# MCU.net
KiCad netlist of a schematic drawn in Altium Designer
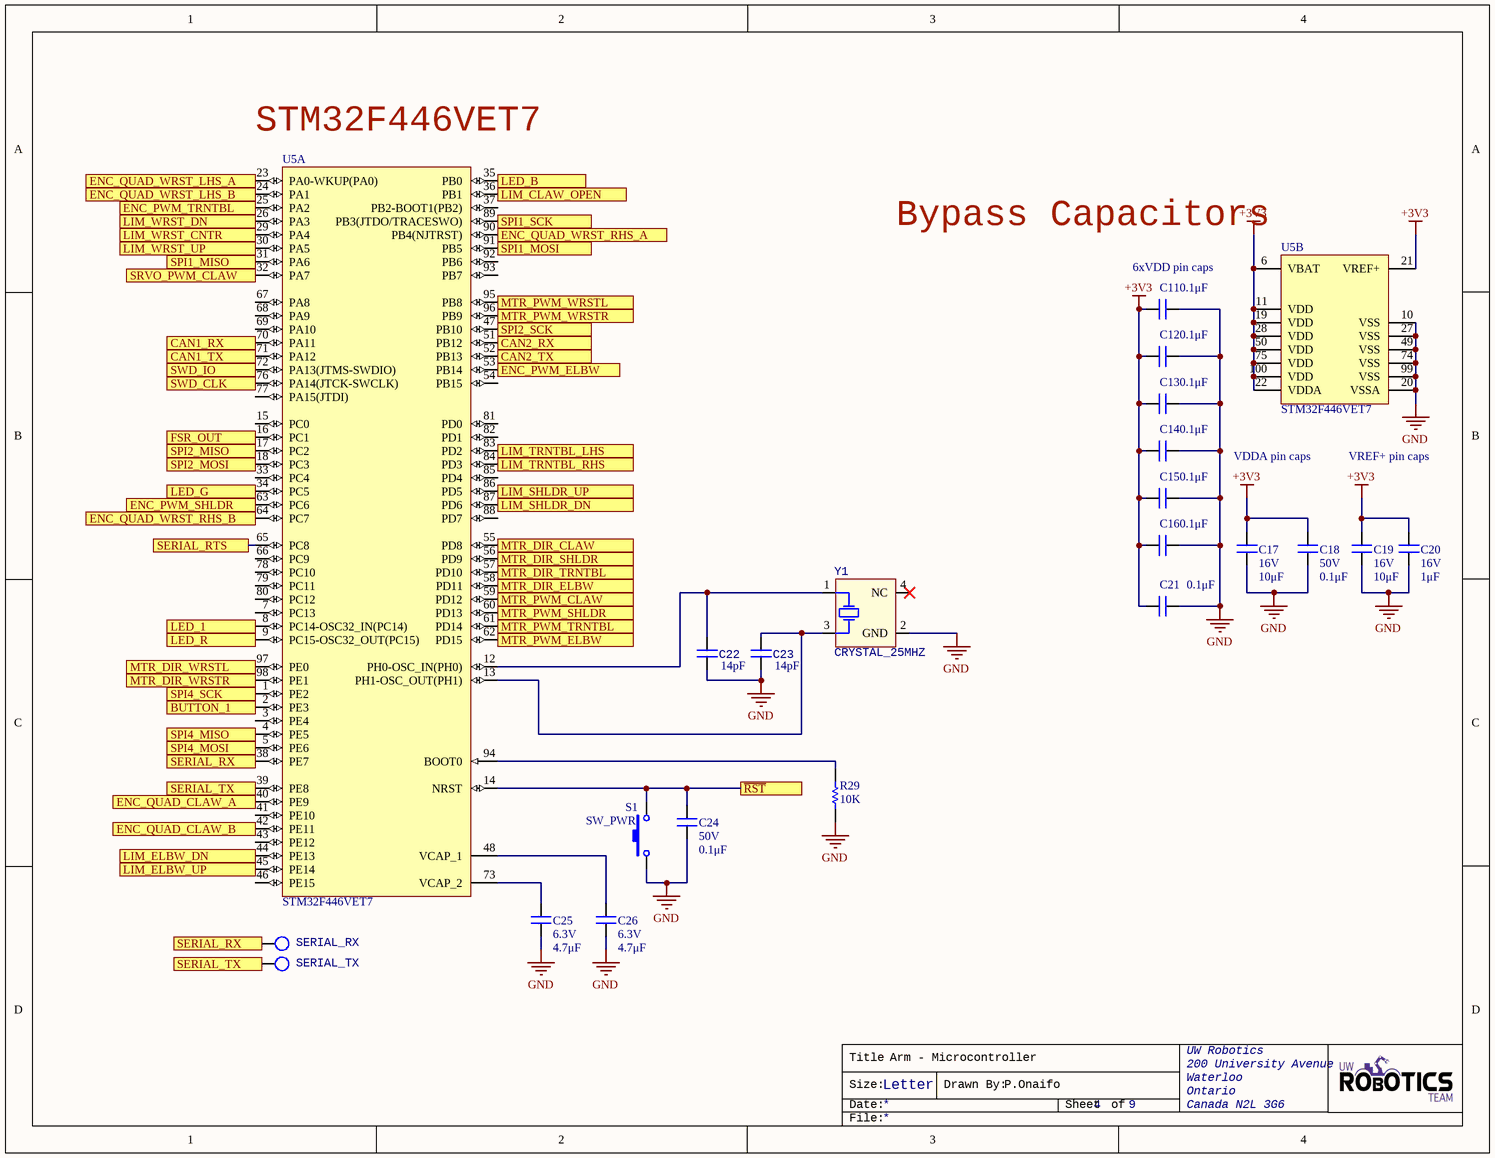
[diagram p0: MCU.SchDoc]

(export (version "E")
  (design (tool "Eeschema 10.0.6"))
  (components
    (comp (ref "C11")
      (value "0.1μF")
      (footprint "CAPC0603(1608)55_N")
      (description "CAP CER 0.1UF 50V X7R 0603")
      (fields (field (name "Comment") "CAP_0.1uF_50V_0603"))
      (libsource (lib "UWRT_Schematic_Library_2020") (part "CAP_0.1uF_50V_0603"))
    )
    (comp (ref "C12")
      (value "0.1μF")
      (footprint "CAPC0603(1608)55_N")
      (description "CAP CER 0.1UF 50V X7R 0603")
      (fields (field (name "Comment") "CAP_0.1uF_50V_0603"))
      (libsource (lib "UWRT_Schematic_Library_2020") (part "CAP_0.1uF_50V_0603"))
    )
    (comp (ref "C13")
      (value "0.1μF")
      (footprint "CAPC0603(1608)55_N")
      (description "CAP CER 0.1UF 50V X7R 0603")
      (fields (field (name "Comment") "CAP_0.1uF_50V_0603"))
      (libsource (lib "UWRT_Schematic_Library_2020") (part "CAP_0.1uF_50V_0603"))
    )
    (comp (ref "C14")
      (value "0.1μF")
      (footprint "CAPC0603(1608)55_N")
      (description "CAP CER 0.1UF 50V X7R 0603")
      (fields (field (name "Comment") "CAP_0.1uF_50V_0603"))
      (libsource (lib "UWRT_Schematic_Library_2020") (part "CAP_0.1uF_50V_0603"))
    )
    (comp (ref "C15")
      (value "0.1μF")
      (footprint "CAPC0603(1608)55_N")
      (description "CAP CER 0.1UF 50V X7R 0603")
      (fields (field (name "Comment") "CAP_0.1uF_50V_0603"))
      (libsource (lib "UWRT_Schematic_Library_2020") (part "CAP_0.1uF_50V_0603"))
    )
    (comp (ref "C16")
      (value "0.1μF")
      (footprint "CAPC0603(1608)55_N")
      (description "CAP CER 0.1UF 50V X7R 0603")
      (fields (field (name "Comment") "CAP_0.1uF_50V_0603"))
      (libsource (lib "UWRT_Schematic_Library_2020") (part "CAP_0.1uF_50V_0603"))
    )
    (comp (ref "C17")
      (value "10μF")
      (footprint "CAPC0603(1608)55_N")
      (description "CAP CER 10000PF 16V X7R 0603")
      (fields (field (name "VOLTAGE RATING") "16V") (field (name "Comment") "CAP_10nF_0603"))
      (libsource (lib "UWRT_Schematic_Library_2020") (part "CAP_10nF_0603"))
    )
    (comp (ref "C18")
      (value "0.1μF")
      (footprint "CAPC0603(1608)55_N")
      (description "CAP CER 0.1UF 50V X7R 0603")
      (fields (field (name "VOLTAGE RATING") "50V") (field (name "Comment") "CAP_0.1uF_50V_0603"))
      (libsource (lib "UWRT_Schematic_Library_2020") (part "CAP_0.1uF_50V_0603"))
    )
    (comp (ref "C19")
      (value "10μF")
      (footprint "CAPC0603(1608)55_N")
      (description "CAP CER 10000PF 16V X7R 0603")
      (fields (field (name "VOLTAGE RATING") "16V") (field (name "Comment") "CAP_10nF_0603"))
      (libsource (lib "UWRT_Schematic_Library_2020") (part "CAP_10nF_0603"))
    )
    (comp (ref "C20")
      (value "1μF")
      (footprint "CAPC0603(1608)55_N")
      (description "CAP CER 1UF 16V Y5V 0603")
      (fields
        (field (name "VOLTAGE RATING") "16V")
        (field (name "MANUFACTURER PART NUMBER") "CC0603ZRY5V7BB105")
        (field (name "Comment") "CAP_1uF_16V_0603")
      )
      (libsource (lib "UWRT_Schematic_Library_2020") (part "CAP_1uF_16V_0603"))
    )
    (comp (ref "C21")
      (value "0.1μF")
      (footprint "CAPC0603(1608)55_N")
      (description "CAP CER 0.1UF 50V X7R 0603")
      (fields (field (name "Comment") "CAP_0.1uF_50V_0603"))
      (libsource (lib "UWRT_Schematic_Library_2020") (part "CAP_0.1uF_50V_0603"))
    )
    (comp (ref "C22")
      (value "14pF")
      (description "CAP CER 14PF 50V C0G/NP0 0603")
      (fields (field (name "TOLERANCE") "5%") (field (name "Comment") "CAP_14pF_50V_0603"))
      (libsource (lib "UWRT_Schematic_Library_2020") (part "CAP_14pF_50V_0603"))
    )
    (comp (ref "C23")
      (value "14pF")
      (description "CAP CER 14PF 50V C0G/NP0 0603")
      (fields (field (name "TOLERANCE") "5%") (field (name "Comment") "CAP_14pF_50V_0603"))
      (libsource (lib "UWRT_Schematic_Library_2020") (part "CAP_14pF_50V_0603"))
    )
    (comp (ref "C24")
      (value "0.1μF")
      (footprint "CAPC0603(1608)55_N")
      (description "CAP CER 0.1UF 50V X7R 0603")
      (fields (field (name "VOLTAGE RATING") "50V") (field (name "Comment") "CAP_0.1uF_50V_0603"))
      (libsource (lib "UWRT_Schematic_Library_2020") (part "CAP_0.1uF_50V_0603"))
    )
    (comp (ref "C25")
      (value "4.7μF")
      (footprint "CAPC0603(1608)55_N")
      (description "CAP CER 4.7UF 6.3V X5R 0603")
      (fields (field (name "VOLTAGE RATING") "6.3V") (field (name "Comment") "CAP_4.7uF_0603"))
      (libsource (lib "UWRT_Schematic_Library_2020") (part "CAP_4.7uF_0603"))
    )
    (comp (ref "C26")
      (value "4.7μF")
      (footprint "CAPC0603(1608)55_N")
      (description "CAP CER 4.7UF 6.3V X5R 0603")
      (fields (field (name "VOLTAGE RATING") "6.3V") (field (name "Comment") "CAP_4.7uF_0603"))
      (libsource (lib "UWRT_Schematic_Library_2020") (part "CAP_4.7uF_0603"))
    )
    (comp (ref "R29")
      (value "10K")
      (footprint "RESC0603(1608)_N")
      (description "RES SMD 10K OHM 5% 1/10W 0603")
      (fields (field (name "MANUFACTURER") "Yageo") (field (name "MPN") "RC0603JR-0710KL"))
      (libsource (lib "UWRT_Schematic_Library_2020") (part "RES_10K_0603"))
    )
    (comp (ref "S1")
      (value "SW_PWR")
      (footprint "PTS830GM140")
      (description "Power Switch (Red)")
      (libsource (lib "UWRT_Schematic_Library_2020") (part "SW_PWR"))
    )
    (comp (ref "SERIAL_RX")
      (value "TESTPOINT_LOOP")
      (footprint "TESTPOINT_LOOP")
      (description "Loop testpoint through-hole pad")
      (libsource (lib "UWRT_Schematic_Library_2020") (part "TESTPOINT_LOOP"))
    )
    (comp (ref "SERIAL_TX")
      (value "TESTPOINT_LOOP")
      (footprint "TESTPOINT_LOOP")
      (description "Loop testpoint through-hole pad")
      (libsource (lib "UWRT_Schematic_Library_2020") (part "TESTPOINT_LOOP"))
    )
    (comp (ref "U5")
      (value "STM32F446VET7")
      (footprint "STM-LQFP100_L")
      (libsource (lib "Altium Content Vault") (part "MC-ARM-STM32F446-LQFP100"))
    )
    (comp (ref "Y1")
      (value "CRYSTAL_25MHZ")
      (footprint "SOIC254P1016X440-4N")
      (description "CRYSTAL 25.0000MHZ 12PF SMD")
      (libsource (lib "UWRT_Schematic_Library_2020") (part "CRYSTAL_25MHZ"))
    )
  )
  (nets
    (net (code "1") (name "+3V3") (class "Default")
      (node (ref "C11") (pin "1") (pinfunction "1_1") (pintype "passive"))
      (node (ref "C12") (pin "1") (pinfunction "1_1") (pintype "passive"))
      (node (ref "C13") (pin "1") (pinfunction "1_1") (pintype "passive"))
      (node (ref "C14") (pin "1") (pinfunction "1_1") (pintype "passive"))
      (node (ref "C15") (pin "1") (pinfunction "1_1") (pintype "passive"))
      (node (ref "C16") (pin "1") (pinfunction "1_1") (pintype "passive"))
      (node (ref "C17") (pin "2") (pinfunction "2_2") (pintype "passive"))
      (node (ref "C18") (pin "2") (pinfunction "2_2") (pintype "passive"))
      (node (ref "C19") (pin "1") (pinfunction "1_1") (pintype "passive"))
      (node (ref "C20") (pin "2") (pinfunction "2_2") (pintype "passive"))
      (node (ref "C21") (pin "1") (pinfunction "1_1") (pintype "passive"))
      (node (ref "U5") (pin "100") (pinfunction "VDD_100") (pintype "power_in"))
      (node (ref "U5") (pin "11") (pinfunction "VDD_11") (pintype "power_in"))
      (node (ref "U5") (pin "19") (pinfunction "VDD_19") (pintype "power_in"))
      (node (ref "U5") (pin "21") (pinfunction "VREF+_21") (pintype "power_in"))
      (node (ref "U5") (pin "22") (pinfunction "VDDA_22") (pintype "power_in"))
      (node (ref "U5") (pin "28") (pinfunction "VDD_28") (pintype "power_in"))
      (node (ref "U5") (pin "50") (pinfunction "VDD_50") (pintype "power_in"))
      (node (ref "U5") (pin "6") (pinfunction "VBAT_6") (pintype "power_in"))
      (node (ref "U5") (pin "75") (pinfunction "VDD_75") (pintype "power_in"))
    )
    (net (code "2") (name "/BUTTON_1") (class "Default")
      (node (ref "U5") (pin "2") (pinfunction "PE3_2") (pintype "bidirectional"))
    )
    (net (code "3") (name "/CAN1_RX") (class "Default")
      (node (ref "U5") (pin "70") (pinfunction "PA11_70") (pintype "bidirectional"))
    )
    (net (code "4") (name "/CAN1_TX") (class "Default")
      (node (ref "U5") (pin "71") (pinfunction "PA12_71") (pintype "bidirectional"))
    )
    (net (code "5") (name "/CAN2_RX") (class "Default")
      (node (ref "U5") (pin "51") (pinfunction "PB12_51") (pintype "bidirectional"))
    )
    (net (code "6") (name "/CAN2_TX") (class "Default")
      (node (ref "U5") (pin "52") (pinfunction "PB13_52") (pintype "bidirectional"))
    )
    (net (code "7") (name "/ENC_PWM_ELBW") (class "Default")
      (node (ref "U5") (pin "53") (pinfunction "PB14_53") (pintype "bidirectional"))
    )
    (net (code "8") (name "/ENC_PWM_SHLDR") (class "Default")
      (node (ref "U5") (pin "63") (pinfunction "PC6_63") (pintype "bidirectional"))
    )
    (net (code "9") (name "/ENC_PWM_TRNTBL") (class "Default")
      (node (ref "U5") (pin "25") (pinfunction "PA2_25") (pintype "bidirectional"))
    )
    (net (code "10") (name "/ENC_QUAD_CLAW_A") (class "Default")
      (node (ref "U5") (pin "40") (pinfunction "PE9_40") (pintype "bidirectional"))
    )
    (net (code "11") (name "/ENC_QUAD_CLAW_B") (class "Default")
      (node (ref "U5") (pin "42") (pinfunction "PE11_42") (pintype "bidirectional"))
    )
    (net (code "12") (name "/ENC_QUAD_WRST_LHS_A") (class "Default")
      (node (ref "U5") (pin "23") (pinfunction "PA0-WKUP(PA0)_23") (pintype "bidirectional"))
    )
    (net (code "13") (name "/ENC_QUAD_WRST_LHS_B") (class "Default")
      (node (ref "U5") (pin "24") (pinfunction "PA1_24") (pintype "bidirectional"))
    )
    (net (code "14") (name "/ENC_QUAD_WRST_RHS_A") (class "Default")
      (node (ref "U5") (pin "90") (pinfunction "PB4(NJTRST)_90") (pintype "bidirectional"))
    )
    (net (code "15") (name "/ENC_QUAD_WRST_RHS_B") (class "Default")
      (node (ref "U5") (pin "64") (pinfunction "PC7_64") (pintype "bidirectional"))
    )
    (net (code "16") (name "/FSR_OUT") (class "Default")
      (node (ref "U5") (pin "16") (pinfunction "PC1_16") (pintype "bidirectional"))
    )
    (net (code "17") (name "/LED_1") (class "Default")
      (node (ref "U5") (pin "8") (pinfunction "PC14-OSC32_IN(PC14)_8") (pintype "bidirectional"))
    )
    (net (code "18") (name "/LED_B") (class "Default")
      (node (ref "U5") (pin "35") (pinfunction "PB0_35") (pintype "bidirectional"))
    )
    (net (code "19") (name "/LED_G") (class "Default")
      (node (ref "U5") (pin "34") (pinfunction "PC5_34") (pintype "bidirectional"))
    )
    (net (code "20") (name "/LED_R") (class "Default")
      (node (ref "U5") (pin "9") (pinfunction "PC15-OSC32_OUT(PC15)_9") (pintype "bidirectional"))
    )
    (net (code "21") (name "/LIM_CLAW_OPEN") (class "Default")
      (node (ref "U5") (pin "36") (pinfunction "PB1_36") (pintype "bidirectional"))
    )
    (net (code "22") (name "/LIM_ELBW_DN") (class "Default")
      (node (ref "U5") (pin "44") (pinfunction "PE13_44") (pintype "bidirectional"))
    )
    (net (code "23") (name "/LIM_ELBW_UP") (class "Default")
      (node (ref "U5") (pin "45") (pinfunction "PE14_45") (pintype "bidirectional"))
    )
    (net (code "24") (name "/LIM_SHLDR_DN") (class "Default")
      (node (ref "U5") (pin "87") (pinfunction "PD6_87") (pintype "bidirectional"))
    )
    (net (code "25") (name "/LIM_SHLDR_UP") (class "Default")
      (node (ref "U5") (pin "86") (pinfunction "PD5_86") (pintype "bidirectional"))
    )
    (net (code "26") (name "/LIM_TRNTBL_LHS") (class "Default")
      (node (ref "U5") (pin "83") (pinfunction "PD2_83") (pintype "bidirectional"))
    )
    (net (code "27") (name "/LIM_TRNTBL_RHS") (class "Default")
      (node (ref "U5") (pin "84") (pinfunction "PD3_84") (pintype "bidirectional"))
    )
    (net (code "28") (name "/LIM_WRST_CNTR") (class "Default")
      (node (ref "U5") (pin "29") (pinfunction "PA4_29") (pintype "bidirectional"))
    )
    (net (code "29") (name "/LIM_WRST_DN") (class "Default")
      (node (ref "U5") (pin "26") (pinfunction "PA3_26") (pintype "bidirectional"))
    )
    (net (code "30") (name "/LIM_WRST_UP") (class "Default")
      (node (ref "U5") (pin "30") (pinfunction "PA5_30") (pintype "bidirectional"))
    )
    (net (code "31") (name "/MTR_DIR_CLAW") (class "Default")
      (node (ref "U5") (pin "55") (pinfunction "PD8_55") (pintype "bidirectional"))
    )
    (net (code "32") (name "/MTR_DIR_ELBW") (class "Default")
      (node (ref "U5") (pin "58") (pinfunction "PD11_58") (pintype "bidirectional"))
    )
    (net (code "33") (name "/MTR_DIR_SHLDR") (class "Default")
      (node (ref "U5") (pin "56") (pinfunction "PD9_56") (pintype "bidirectional"))
    )
    (net (code "34") (name "/MTR_DIR_TRNTBL") (class "Default")
      (node (ref "U5") (pin "57") (pinfunction "PD10_57") (pintype "bidirectional"))
    )
    (net (code "35") (name "/MTR_DIR_WRSTL") (class "Default")
      (node (ref "U5") (pin "97") (pinfunction "PE0_97") (pintype "bidirectional"))
    )
    (net (code "36") (name "/MTR_DIR_WRSTR") (class "Default")
      (node (ref "U5") (pin "98") (pinfunction "PE1_98") (pintype "bidirectional"))
    )
    (net (code "37") (name "/MTR_PWM_CLAW") (class "Default")
      (node (ref "U5") (pin "59") (pinfunction "PD12_59") (pintype "bidirectional"))
    )
    (net (code "38") (name "/MTR_PWM_ELBW") (class "Default")
      (node (ref "U5") (pin "62") (pinfunction "PD15_62") (pintype "bidirectional"))
    )
    (net (code "39") (name "/MTR_PWM_SHLDR") (class "Default")
      (node (ref "U5") (pin "60") (pinfunction "PD13_60") (pintype "bidirectional"))
    )
    (net (code "40") (name "/MTR_PWM_TRNTBL") (class "Default")
      (node (ref "U5") (pin "61") (pinfunction "PD14_61") (pintype "bidirectional"))
    )
    (net (code "41") (name "/MTR_PWM_WRSTL") (class "Default")
      (node (ref "U5") (pin "95") (pinfunction "PB8_95") (pintype "bidirectional"))
    )
    (net (code "42") (name "/MTR_PWM_WRSTR") (class "Default")
      (node (ref "U5") (pin "96") (pinfunction "PB9_96") (pintype "bidirectional"))
    )
    (net (code "43") (name "/SERIAL_RTS") (class "Default")
      (node (ref "U5") (pin "65") (pinfunction "PC8_65") (pintype "bidirectional"))
    )
    (net (code "44") (name "/SERIAL_RX") (class "Default")
      (node (ref "SERIAL_RX") (pin "1") (pintype "passive"))
      (node (ref "U5") (pin "38") (pinfunction "PE7_38") (pintype "bidirectional"))
    )
    (net (code "45") (name "/SERIAL_TX") (class "Default")
      (node (ref "SERIAL_TX") (pin "1") (pintype "passive"))
      (node (ref "U5") (pin "39") (pinfunction "PE8_39") (pintype "bidirectional"))
    )
    (net (code "46") (name "/SPI1_MISO") (class "Default")
      (node (ref "U5") (pin "31") (pinfunction "PA6_31") (pintype "bidirectional"))
    )
    (net (code "47") (name "/SPI1_MOSI") (class "Default")
      (node (ref "U5") (pin "91") (pinfunction "PB5_91") (pintype "bidirectional"))
    )
    (net (code "48") (name "/SPI1_SCK") (class "Default")
      (node (ref "U5") (pin "89") (pinfunction "PB3(JTDO/TRACESWO)_89") (pintype "bidirectional"))
    )
    (net (code "49") (name "/SPI2_MISO") (class "Default")
      (node (ref "U5") (pin "17") (pinfunction "PC2_17") (pintype "bidirectional"))
    )
    (net (code "50") (name "/SPI2_MOSI") (class "Default")
      (node (ref "U5") (pin "18") (pinfunction "PC3_18") (pintype "bidirectional"))
    )
    (net (code "51") (name "/SPI2_SCK") (class "Default")
      (node (ref "U5") (pin "47") (pinfunction "PB10_47") (pintype "bidirectional"))
    )
    (net (code "52") (name "/SPI4_MISO") (class "Default")
      (node (ref "U5") (pin "4") (pinfunction "PE5_4") (pintype "bidirectional"))
    )
    (net (code "53") (name "/SPI4_MOSI") (class "Default")
      (node (ref "U5") (pin "5") (pinfunction "PE6_5") (pintype "bidirectional"))
    )
    (net (code "54") (name "/SPI4_SCK") (class "Default")
      (node (ref "U5") (pin "1") (pinfunction "PE2_1") (pintype "bidirectional"))
    )
    (net (code "55") (name "/SRVO_PWM_CLAW") (class "Default")
      (node (ref "U5") (pin "32") (pinfunction "PA7_32") (pintype "bidirectional"))
    )
    (net (code "56") (name "/SWD_CLK") (class "Default")
      (node (ref "U5") (pin "76") (pinfunction "PA14(JTCK-SWCLK)_76") (pintype "bidirectional"))
    )
    (net (code "57") (name "/SWD_IO") (class "Default")
      (node (ref "U5") (pin "72") (pinfunction "PA13(JTMS-SWDIO)_72") (pintype "bidirectional"))
    )
    (net (code "58") (name "/~{RST}") (class "Default")
      (node (ref "C24") (pin "2") (pinfunction "2_2") (pintype "passive"))
      (node (ref "S1") (pin "2") (pinfunction "2_2") (pintype "passive"))
      (node (ref "U5") (pin "14") (pinfunction "NRST_14") (pintype "bidirectional"))
    )
    (net (code "59") (name "GND") (class "Default")
      (node (ref "C11") (pin "2") (pinfunction "2_2") (pintype "passive"))
      (node (ref "C12") (pin "2") (pinfunction "2_2") (pintype "passive"))
      (node (ref "C13") (pin "2") (pinfunction "2_2") (pintype "passive"))
      (node (ref "C14") (pin "2") (pinfunction "2_2") (pintype "passive"))
      (node (ref "C15") (pin "2") (pinfunction "2_2") (pintype "passive"))
      (node (ref "C16") (pin "2") (pinfunction "2_2") (pintype "passive"))
      (node (ref "C17") (pin "1") (pinfunction "1_1") (pintype "passive"))
      (node (ref "C18") (pin "1") (pinfunction "1_1") (pintype "passive"))
      (node (ref "C19") (pin "2") (pinfunction "2_2") (pintype "passive"))
      (node (ref "C20") (pin "1") (pinfunction "1_1") (pintype "passive"))
      (node (ref "C21") (pin "2") (pinfunction "2_2") (pintype "passive"))
      (node (ref "C22") (pin "1") (pinfunction "1_1") (pintype "passive"))
      (node (ref "C23") (pin "1") (pinfunction "1_1") (pintype "passive"))
      (node (ref "C24") (pin "1") (pinfunction "1_1") (pintype "passive"))
      (node (ref "C25") (pin "1") (pinfunction "1_1") (pintype "passive"))
      (node (ref "C26") (pin "1") (pinfunction "1_1") (pintype "passive"))
      (node (ref "R29") (pin "2") (pinfunction "2_2") (pintype "passive"))
      (node (ref "S1") (pin "1") (pinfunction "1_1") (pintype "passive"))
      (node (ref "U5") (pin "10") (pinfunction "VSS_10") (pintype "power_in"))
      (node (ref "U5") (pin "20") (pinfunction "VSSA_20") (pintype "power_in"))
      (node (ref "U5") (pin "27") (pinfunction "VSS_27") (pintype "power_in"))
      (node (ref "U5") (pin "49") (pinfunction "VSS_49") (pintype "power_in"))
      (node (ref "U5") (pin "74") (pinfunction "VSS_74") (pintype "power_in"))
      (node (ref "U5") (pin "99") (pinfunction "VSS_99") (pintype "power_in"))
      (node (ref "Y1") (pin "2") (pinfunction "GND_2") (pintype "power_in"))
    )
    (net (code "60") (name "Net-(U5A-BOOT0)") (class "Default")
      (node (ref "R29") (pin "1") (pinfunction "1_1") (pintype "passive"))
      (node (ref "U5") (pin "94") (pinfunction "BOOT0_94") (pintype "input"))
    )
    (net (code "61") (name "Net-(U5A-PH0-OSC_IN(PH0))") (class "Default")
      (node (ref "C22") (pin "2") (pinfunction "2_2") (pintype "passive"))
      (node (ref "U5") (pin "12") (pinfunction "PH0-OSC_IN(PH0)_12") (pintype "bidirectional"))
      (node (ref "Y1") (pin "1") (pinfunction "HOT_1") (pintype "passive"))
    )
    (net (code "62") (name "Net-(U5A-PH1-OSC_OUT(PH1))") (class "Default")
      (node (ref "C23") (pin "2") (pinfunction "2_2") (pintype "passive"))
      (node (ref "U5") (pin "13") (pinfunction "PH1-OSC_OUT(PH1)_13") (pintype "bidirectional"))
      (node (ref "Y1") (pin "3") (pinfunction "HOT_3") (pintype "passive"))
    )
    (net (code "63") (name "Net-(U5A-VCAP_1)") (class "Default")
      (node (ref "C26") (pin "2") (pinfunction "2_2") (pintype "passive"))
      (node (ref "U5") (pin "48") (pinfunction "VCAP_1_48") (pintype "passive"))
    )
    (net (code "64") (name "Net-(U5A-VCAP_2)") (class "Default")
      (node (ref "C25") (pin "2") (pinfunction "2_2") (pintype "passive"))
      (node (ref "U5") (pin "73") (pinfunction "VCAP_2_73") (pintype "passive"))
    )
    (net (code "65") (name "unconnected-(U5A-PA8-Pad67)") (class "Default")
      (node (ref "U5") (pin "67") (pinfunction "PA8_67") (pintype "bidirectional"))
    )
    (net (code "66") (name "unconnected-(U5A-PA9-Pad68)") (class "Default")
      (node (ref "U5") (pin "68") (pinfunction "PA9_68") (pintype "bidirectional"))
    )
    (net (code "67") (name "unconnected-(U5A-PA10-Pad69)") (class "Default")
      (node (ref "U5") (pin "69") (pinfunction "PA10_69") (pintype "bidirectional"))
    )
    (net (code "68") (name "unconnected-(U5A-PA15(JTDI)-Pad77)") (class "Default")
      (node (ref "U5") (pin "77") (pinfunction "PA15(JTDI)_77") (pintype "bidirectional"))
    )
    (net (code "69") (name "unconnected-(U5A-PB2-BOOT1(PB2)-Pad37)") (class "Default")
      (node (ref "U5") (pin "37") (pinfunction "PB2-BOOT1(PB2)_37") (pintype "bidirectional"))
    )
    (net (code "70") (name "unconnected-(U5A-PB6-Pad92)") (class "Default")
      (node (ref "U5") (pin "92") (pinfunction "PB6_92") (pintype "bidirectional"))
    )
    (net (code "71") (name "unconnected-(U5A-PB7-Pad93)") (class "Default")
      (node (ref "U5") (pin "93") (pinfunction "PB7_93") (pintype "bidirectional"))
    )
    (net (code "72") (name "unconnected-(U5A-PB15-Pad54)") (class "Default")
      (node (ref "U5") (pin "54") (pinfunction "PB15_54") (pintype "bidirectional"))
    )
    (net (code "73") (name "unconnected-(U5A-PC0-Pad15)") (class "Default")
      (node (ref "U5") (pin "15") (pinfunction "PC0_15") (pintype "bidirectional"))
    )
    (net (code "74") (name "unconnected-(U5A-PC4-Pad33)") (class "Default")
      (node (ref "U5") (pin "33") (pinfunction "PC4_33") (pintype "bidirectional"))
    )
    (net (code "75") (name "unconnected-(U5A-PC9-Pad66)") (class "Default")
      (node (ref "U5") (pin "66") (pinfunction "PC9_66") (pintype "bidirectional"))
    )
    (net (code "76") (name "unconnected-(U5A-PC10-Pad78)") (class "Default")
      (node (ref "U5") (pin "78") (pinfunction "PC10_78") (pintype "bidirectional"))
    )
    (net (code "77") (name "unconnected-(U5A-PC11-Pad79)") (class "Default")
      (node (ref "U5") (pin "79") (pinfunction "PC11_79") (pintype "bidirectional"))
    )
    (net (code "78") (name "unconnected-(U5A-PC12-Pad80)") (class "Default")
      (node (ref "U5") (pin "80") (pinfunction "PC12_80") (pintype "bidirectional"))
    )
    (net (code "79") (name "unconnected-(U5A-PC13-Pad7)") (class "Default")
      (node (ref "U5") (pin "7") (pinfunction "PC13_7") (pintype "bidirectional"))
    )
    (net (code "80") (name "unconnected-(U5A-PD0-Pad81)") (class "Default")
      (node (ref "U5") (pin "81") (pinfunction "PD0_81") (pintype "bidirectional"))
    )
    (net (code "81") (name "unconnected-(U5A-PD1-Pad82)") (class "Default")
      (node (ref "U5") (pin "82") (pinfunction "PD1_82") (pintype "bidirectional"))
    )
    (net (code "82") (name "unconnected-(U5A-PD4-Pad85)") (class "Default")
      (node (ref "U5") (pin "85") (pinfunction "PD4_85") (pintype "bidirectional"))
    )
    (net (code "83") (name "unconnected-(U5A-PD7-Pad88)") (class "Default")
      (node (ref "U5") (pin "88") (pinfunction "PD7_88") (pintype "bidirectional"))
    )
    (net (code "84") (name "unconnected-(U5A-PE4-Pad3)") (class "Default")
      (node (ref "U5") (pin "3") (pinfunction "PE4_3") (pintype "bidirectional"))
    )
    (net (code "85") (name "unconnected-(U5A-PE10-Pad41)") (class "Default")
      (node (ref "U5") (pin "41") (pinfunction "PE10_41") (pintype "bidirectional"))
    )
    (net (code "86") (name "unconnected-(U5A-PE12-Pad43)") (class "Default")
      (node (ref "U5") (pin "43") (pinfunction "PE12_43") (pintype "bidirectional"))
    )
    (net (code "87") (name "unconnected-(U5A-PE15-Pad46)") (class "Default")
      (node (ref "U5") (pin "46") (pinfunction "PE15_46") (pintype "bidirectional"))
    )
    (net (code "88") (name "unconnected-(Y1-NC-Pad4)") (class "Default")
      (node (ref "Y1") (pin "4") (pinfunction "NC_4") (pintype "passive+no_connect"))
    )
  )
)
